# Indicators.net
KiCad netlist of a schematic drawn in Altium Designer
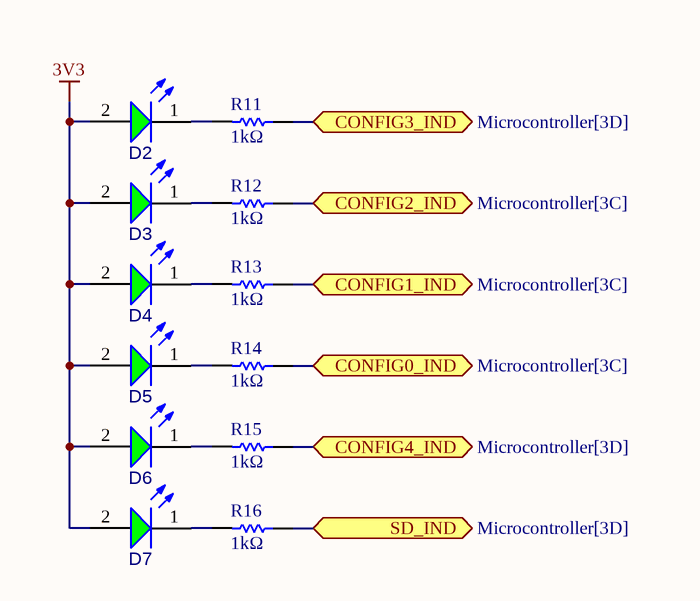
[diagram p0: Indicators.SchDoc]

(export (version "E")
  (design (tool "Eeschema 10.0.6"))
  (components
    (comp (ref "D2")
      (value "150120GS75000")
      (footprint "WL-SMCW_1206_150120xx75000")
      (description "WL-SMCW SMT Mono-Color Chip LED Waterclear")
      (libsource (lib "Altium Content Vault") (part "LED_Green_2A-1K"))
    )
    (comp (ref "D3")
      (value "150120GS75000")
      (footprint "WL-SMCW_1206_150120xx75000")
      (description "WL-SMCW SMT Mono-Color Chip LED Waterclear")
      (libsource (lib "Altium Content Vault") (part "LED_Green_2A-1K"))
    )
    (comp (ref "D4")
      (value "150120GS75000")
      (footprint "WL-SMCW_1206_150120xx75000")
      (description "WL-SMCW SMT Mono-Color Chip LED Waterclear")
      (libsource (lib "Altium Content Vault") (part "LED_Green_2A-1K"))
    )
    (comp (ref "D5")
      (value "150120GS75000")
      (footprint "WL-SMCW_1206_150120xx75000")
      (description "WL-SMCW SMT Mono-Color Chip LED Waterclear")
      (libsource (lib "Altium Content Vault") (part "LED_Green_2A-1K"))
    )
    (comp (ref "D6")
      (value "150120GS75000")
      (footprint "WL-SMCW_1206_150120xx75000")
      (description "WL-SMCW SMT Mono-Color Chip LED Waterclear")
      (libsource (lib "Altium Content Vault") (part "LED_Green_2A-1K"))
    )
    (comp (ref "D7")
      (value "150120GS75000")
      (footprint "WL-SMCW_1206_150120xx75000")
      (description "WL-SMCW SMT Mono-Color Chip LED Waterclear")
      (libsource (lib "Altium Content Vault") (part "LED_Green_2A-1K"))
    )
    (comp (ref "R11")
      (value "1kΩ")
      (footprint "RESC3116X65X40LL10T20")
      (description "Chip Resistor, 1 KOhm, +/- 1%, 0.25 W, -55 to 155 degC, 1206 (3216 Metric), RoHS, Tape and Reel")
      (fields (field (name "TOLERANCE") "1%") (field (name "MANUFACTURER") "Yageo"))
      (libsource (lib "Altium Content Vault") (part "RES-2"))
    )
    (comp (ref "R12")
      (value "1kΩ")
      (footprint "RESC3116X65X40LL10T20")
      (description "Chip Resistor, 1 KOhm, +/- 1%, 0.25 W, -55 to 155 degC, 1206 (3216 Metric), RoHS, Tape and Reel")
      (fields (field (name "TOLERANCE") "1%") (field (name "MANUFACTURER") "Yageo"))
      (libsource (lib "Altium Content Vault") (part "RES-2"))
    )
    (comp (ref "R13")
      (value "1kΩ")
      (footprint "RESC3116X65X40LL10T20")
      (description "Chip Resistor, 1 KOhm, +/- 1%, 0.25 W, -55 to 155 degC, 1206 (3216 Metric), RoHS, Tape and Reel")
      (fields (field (name "TOLERANCE") "1%") (field (name "MANUFACTURER") "Yageo"))
      (libsource (lib "Altium Content Vault") (part "RES-2"))
    )
    (comp (ref "R14")
      (value "1kΩ")
      (footprint "RESC3116X65X40LL10T20")
      (description "Chip Resistor, 1 KOhm, +/- 1%, 0.25 W, -55 to 155 degC, 1206 (3216 Metric), RoHS, Tape and Reel")
      (fields (field (name "TOLERANCE") "1%") (field (name "MANUFACTURER") "Yageo"))
      (libsource (lib "Altium Content Vault") (part "RES-2"))
    )
    (comp (ref "R15")
      (value "1kΩ")
      (footprint "RESC3116X65X40LL10T20")
      (description "Chip Resistor, 1 KOhm, +/- 1%, 0.25 W, -55 to 155 degC, 1206 (3216 Metric), RoHS, Tape and Reel")
      (fields (field (name "TOLERANCE") "1%") (field (name "MANUFACTURER") "Yageo"))
      (libsource (lib "Altium Content Vault") (part "RES-2"))
    )
    (comp (ref "R16")
      (value "1kΩ")
      (footprint "RESC3116X65X40LL10T20")
      (description "Chip Resistor, 1 KOhm, +/- 1%, 0.25 W, -55 to 155 degC, 1206 (3216 Metric), RoHS, Tape and Reel")
      (fields (field (name "TOLERANCE") "1%") (field (name "MANUFACTURER") "Yageo"))
      (libsource (lib "Altium Content Vault") (part "RES-2"))
    )
  )
  (nets
    (net (code "1") (name "/CONFIG0_IND") (class "Default")
      (node (ref "R14") (pin "1") (pinfunction "1_1") (pintype "passive"))
    )
    (net (code "2") (name "/CONFIG1_IND") (class "Default")
      (node (ref "R13") (pin "1") (pinfunction "1_1") (pintype "passive"))
    )
    (net (code "3") (name "/CONFIG2_IND") (class "Default")
      (node (ref "R12") (pin "1") (pinfunction "1_1") (pintype "passive"))
    )
    (net (code "4") (name "/CONFIG3_IND") (class "Default")
      (node (ref "R11") (pin "1") (pinfunction "1_1") (pintype "passive"))
    )
    (net (code "5") (name "/CONFIG4_IND") (class "Default")
      (node (ref "R15") (pin "1") (pinfunction "1_1") (pintype "passive"))
    )
    (net (code "6") (name "/SD_IND") (class "Default")
      (node (ref "R16") (pin "1") (pinfunction "1_1") (pintype "passive"))
    )
    (net (code "7") (name "3V3") (class "Default")
      (node (ref "D2") (pin "2") (pinfunction "A_2") (pintype "passive"))
      (node (ref "D3") (pin "2") (pinfunction "A_2") (pintype "passive"))
      (node (ref "D4") (pin "2") (pinfunction "A_2") (pintype "passive"))
      (node (ref "D5") (pin "2") (pinfunction "A_2") (pintype "passive"))
      (node (ref "D6") (pin "2") (pinfunction "A_2") (pintype "passive"))
      (node (ref "D7") (pin "2") (pinfunction "A_2") (pintype "passive"))
    )
    (net (code "8") (name "Net-(D2-K)") (class "Default")
      (node (ref "D2") (pin "1") (pinfunction "K_1") (pintype "passive"))
      (node (ref "R11") (pin "2") (pinfunction "2_2") (pintype "passive"))
    )
    (net (code "9") (name "Net-(D3-K)") (class "Default")
      (node (ref "D3") (pin "1") (pinfunction "K_1") (pintype "passive"))
      (node (ref "R12") (pin "2") (pinfunction "2_2") (pintype "passive"))
    )
    (net (code "10") (name "Net-(D4-K)") (class "Default")
      (node (ref "D4") (pin "1") (pinfunction "K_1") (pintype "passive"))
      (node (ref "R13") (pin "2") (pinfunction "2_2") (pintype "passive"))
    )
    (net (code "11") (name "Net-(D5-K)") (class "Default")
      (node (ref "D5") (pin "1") (pinfunction "K_1") (pintype "passive"))
      (node (ref "R14") (pin "2") (pinfunction "2_2") (pintype "passive"))
    )
    (net (code "12") (name "Net-(D6-K)") (class "Default")
      (node (ref "D6") (pin "1") (pinfunction "K_1") (pintype "passive"))
      (node (ref "R15") (pin "2") (pinfunction "2_2") (pintype "passive"))
    )
    (net (code "13") (name "Net-(D7-K)") (class "Default")
      (node (ref "D7") (pin "1") (pinfunction "K_1") (pintype "passive"))
      (node (ref "R16") (pin "2") (pinfunction "2_2") (pintype "passive"))
    )
  )
)
